# mixer.net
KiCad netlist of a schematic drawn in EAGLE
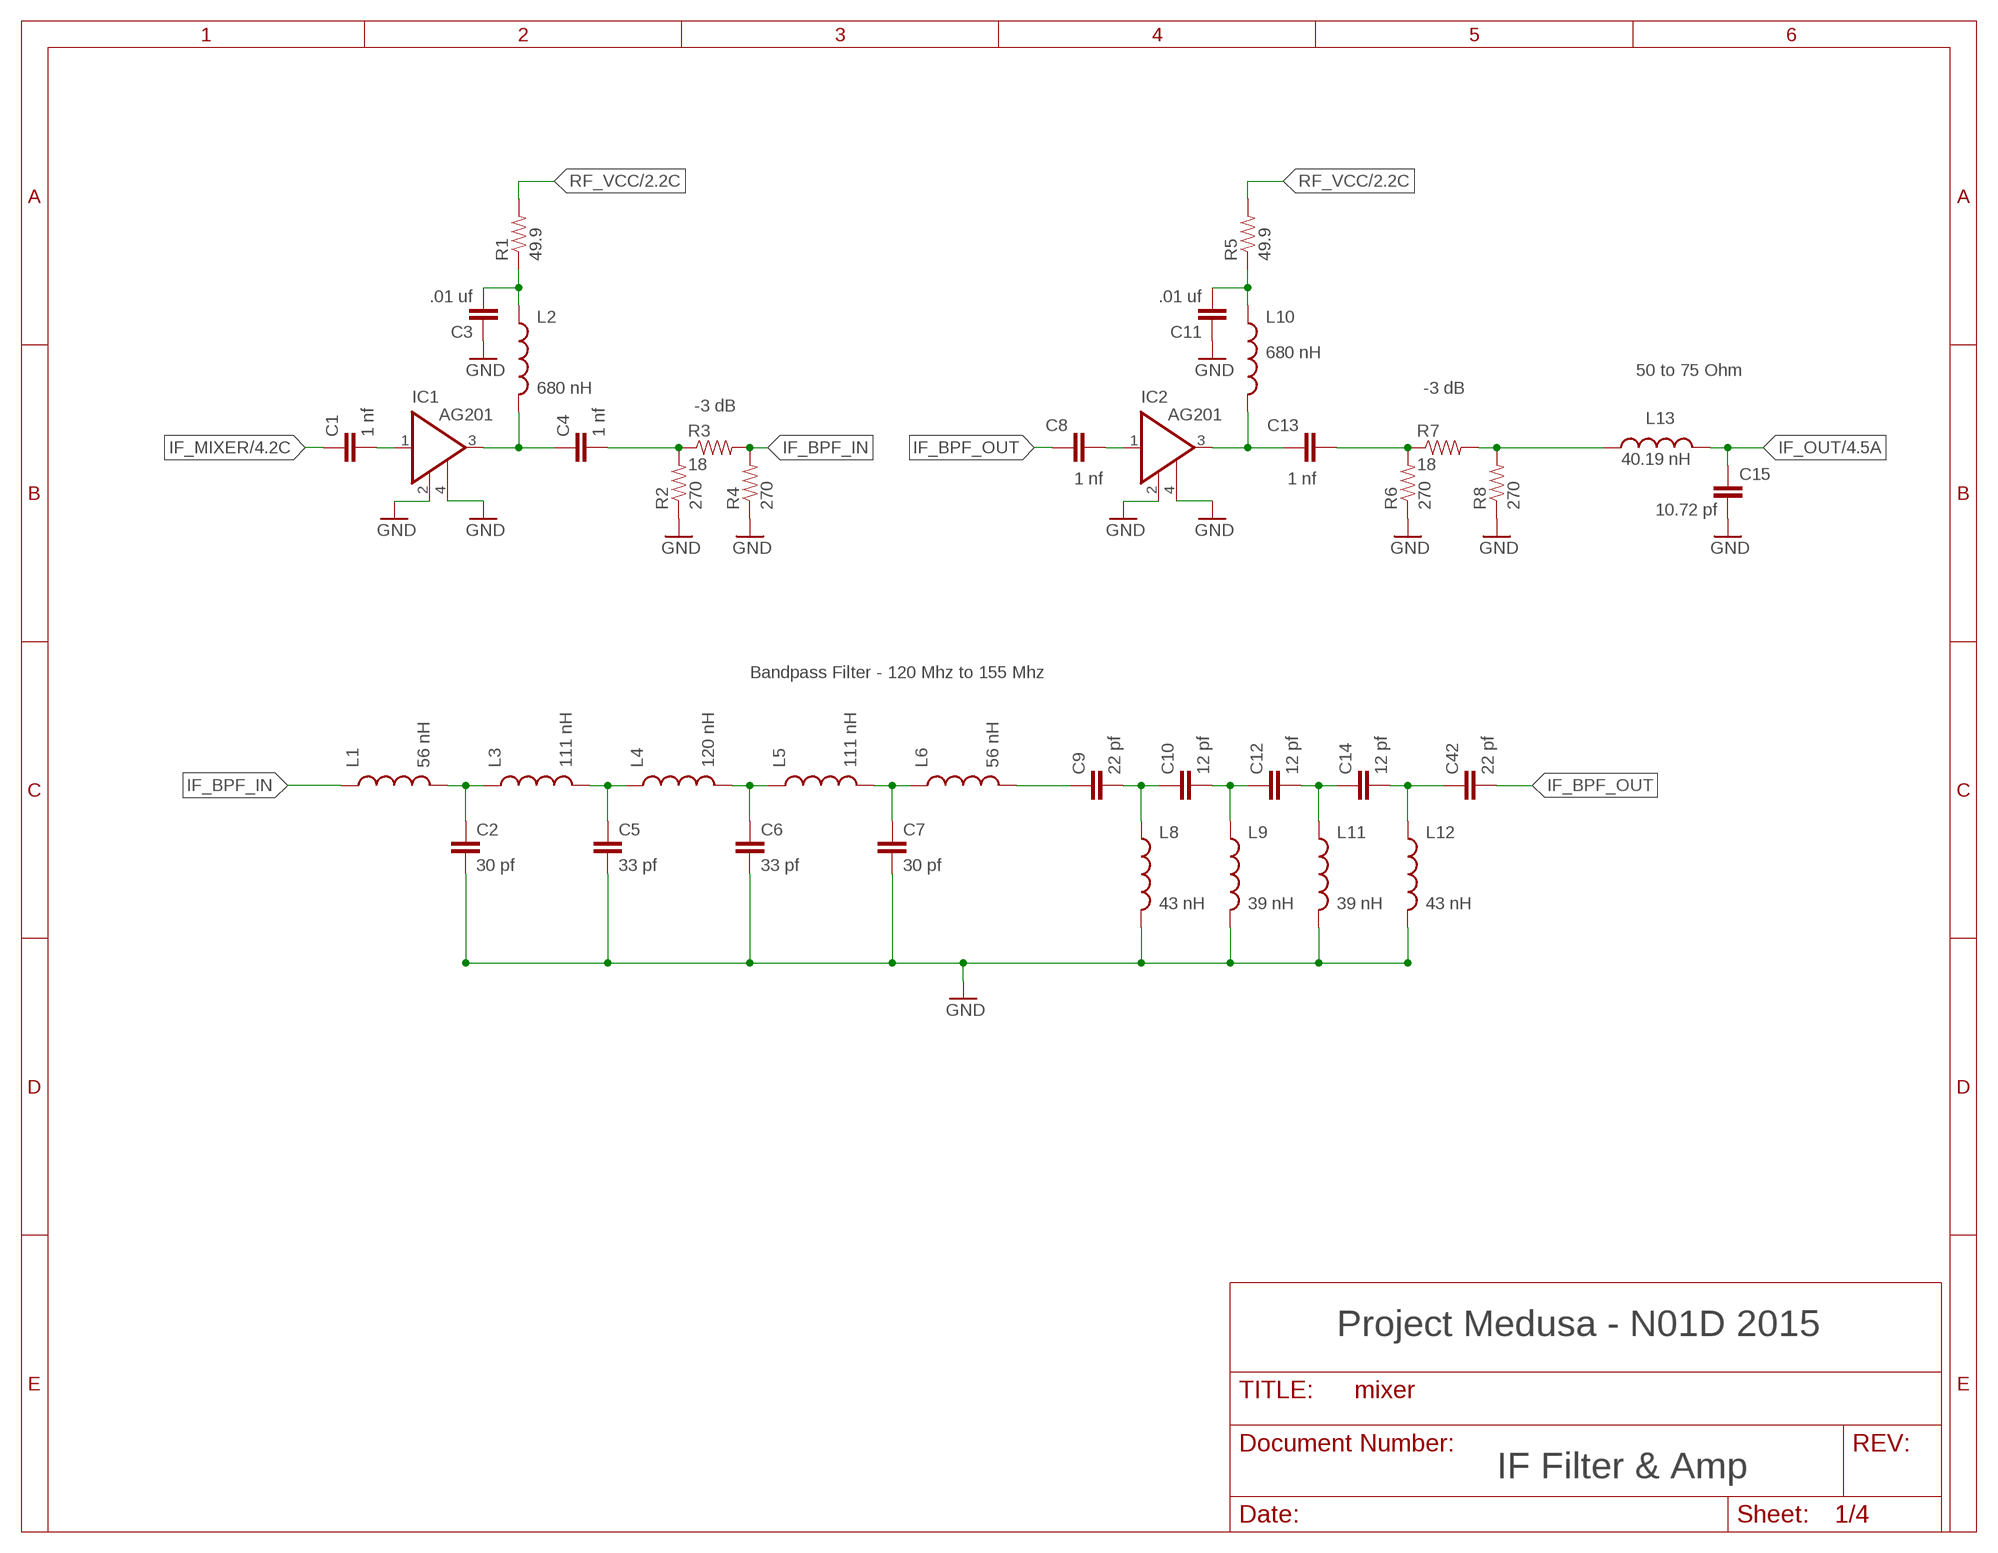
[diagram p0: schematic, sheet 1]
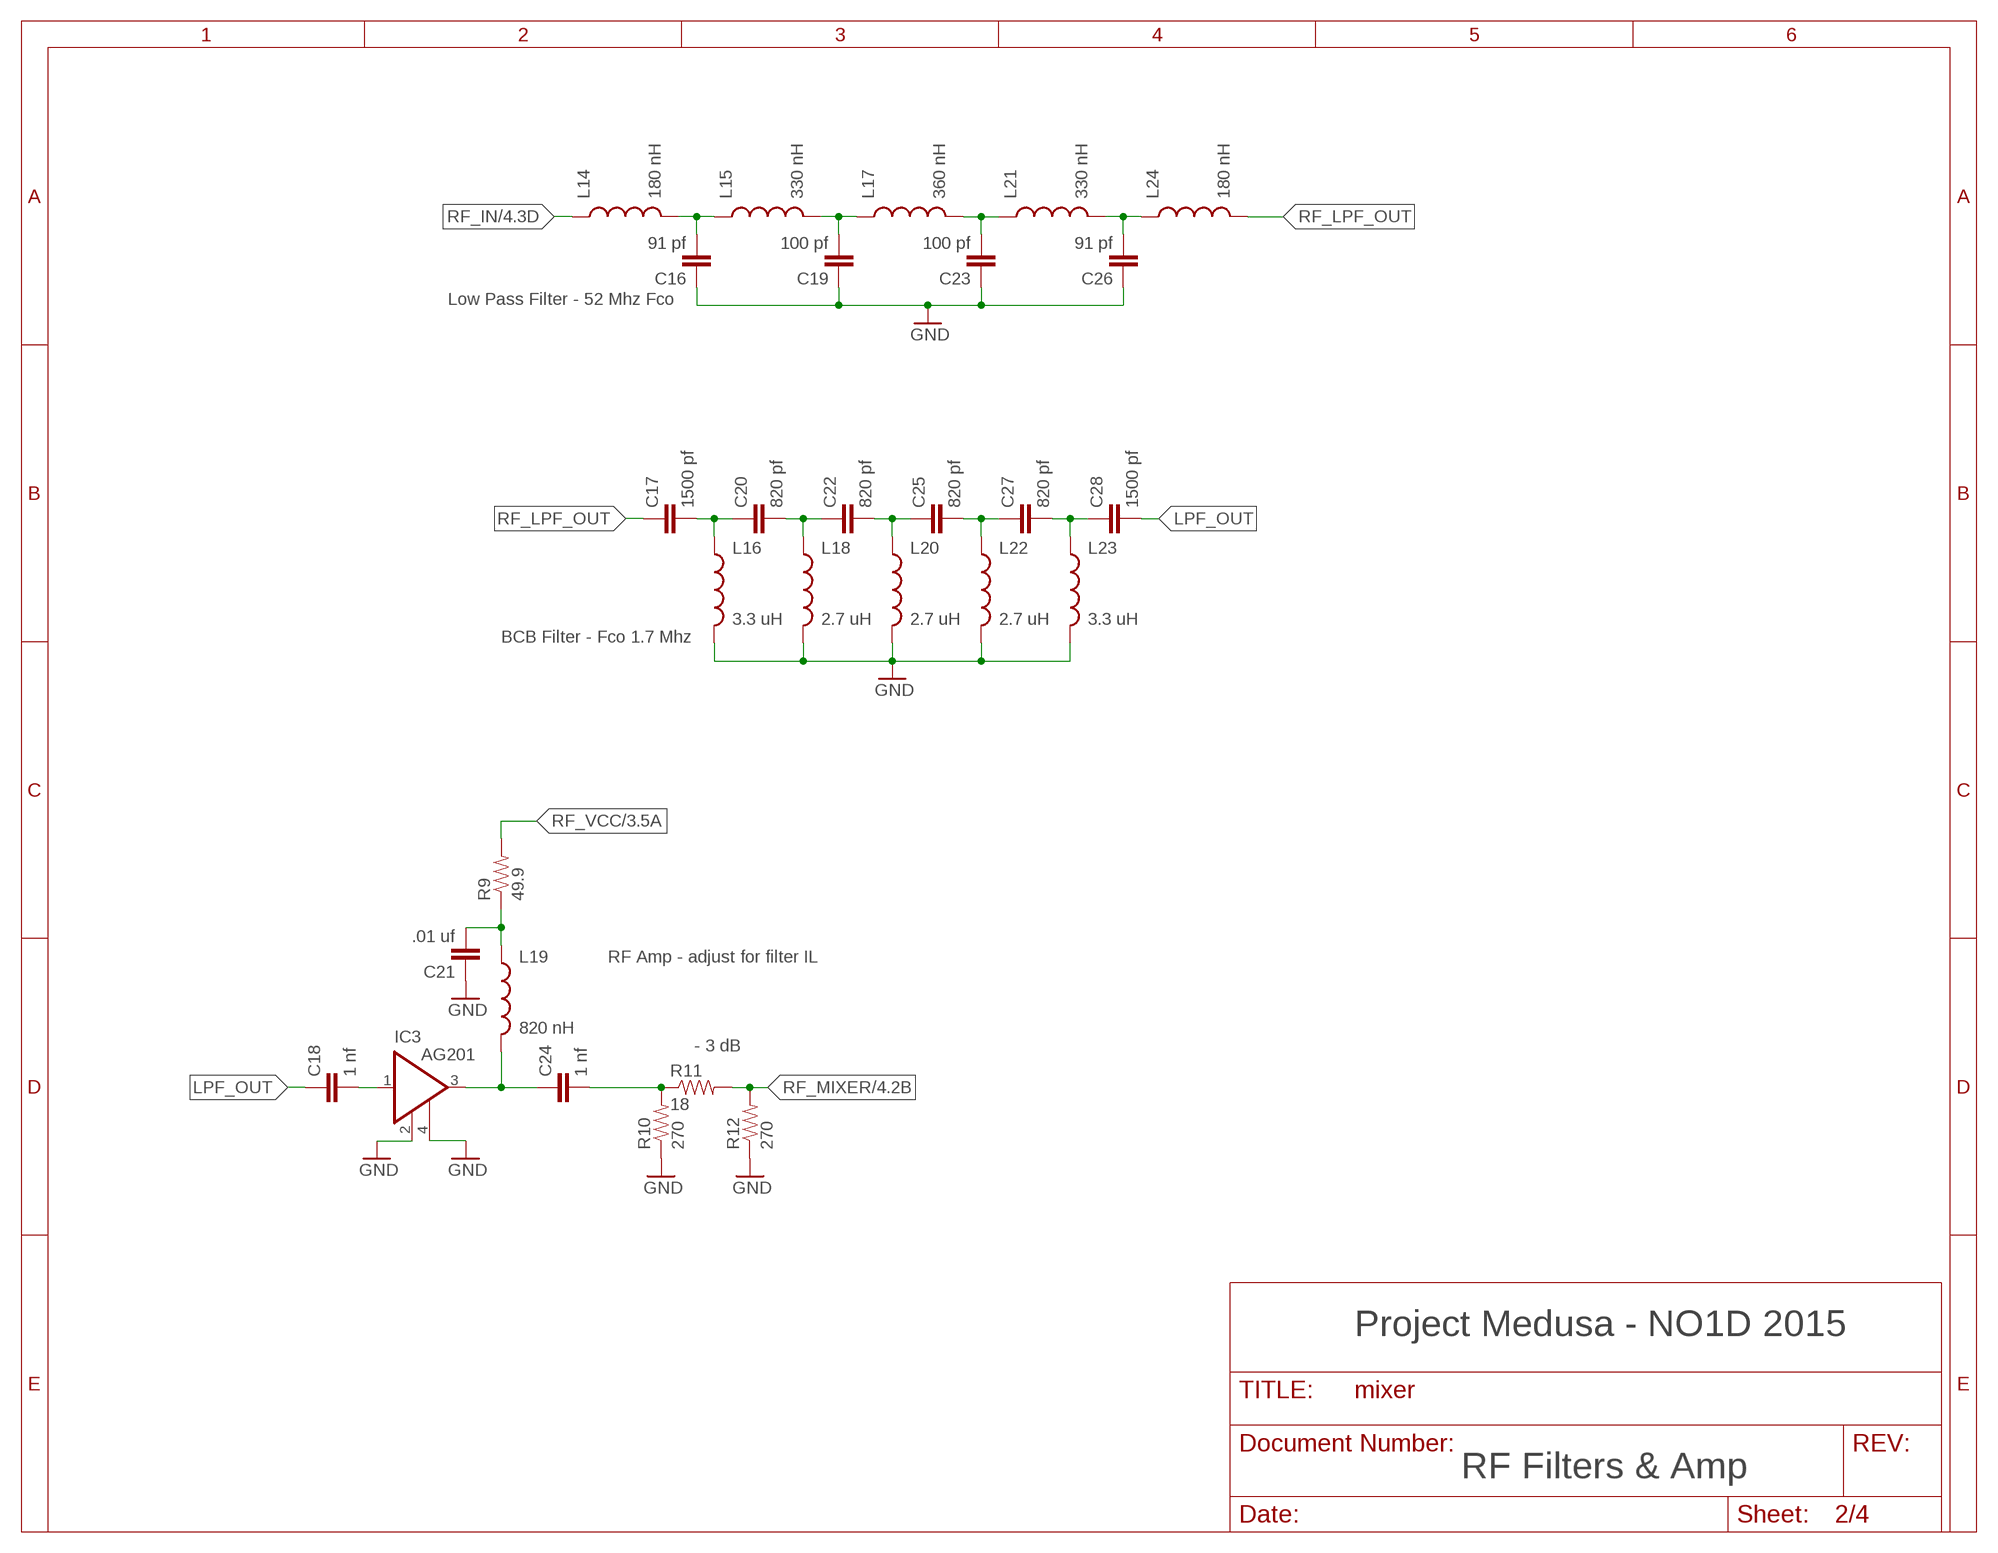
[diagram p1: schematic, sheet 2]
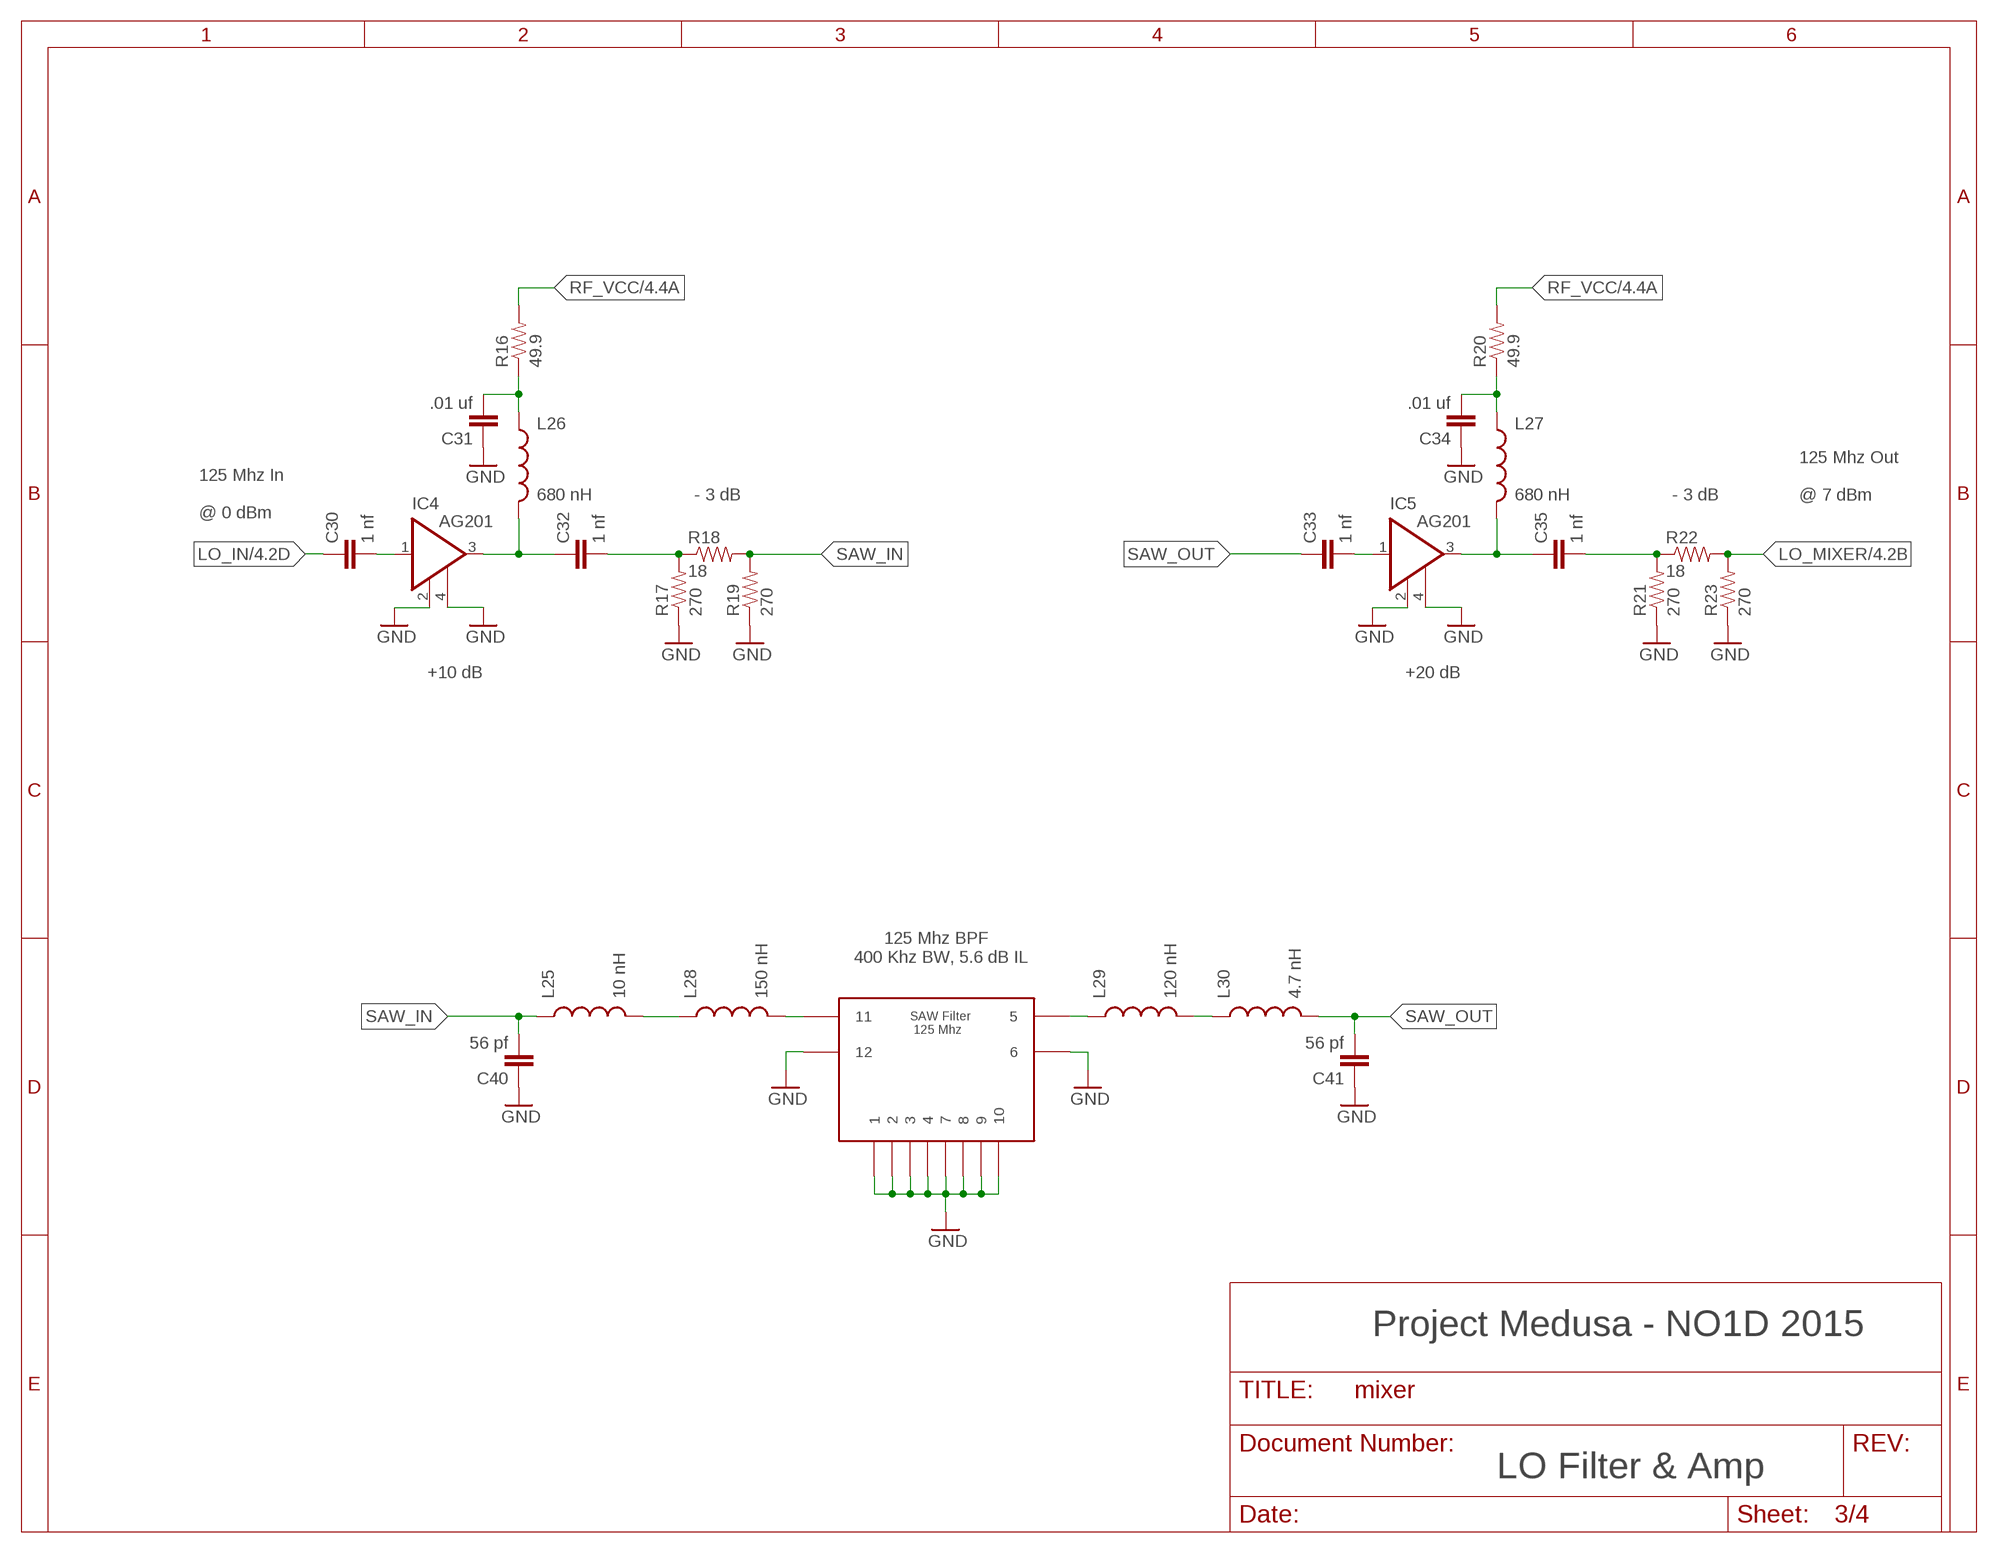
[diagram p2: schematic, sheet 3]
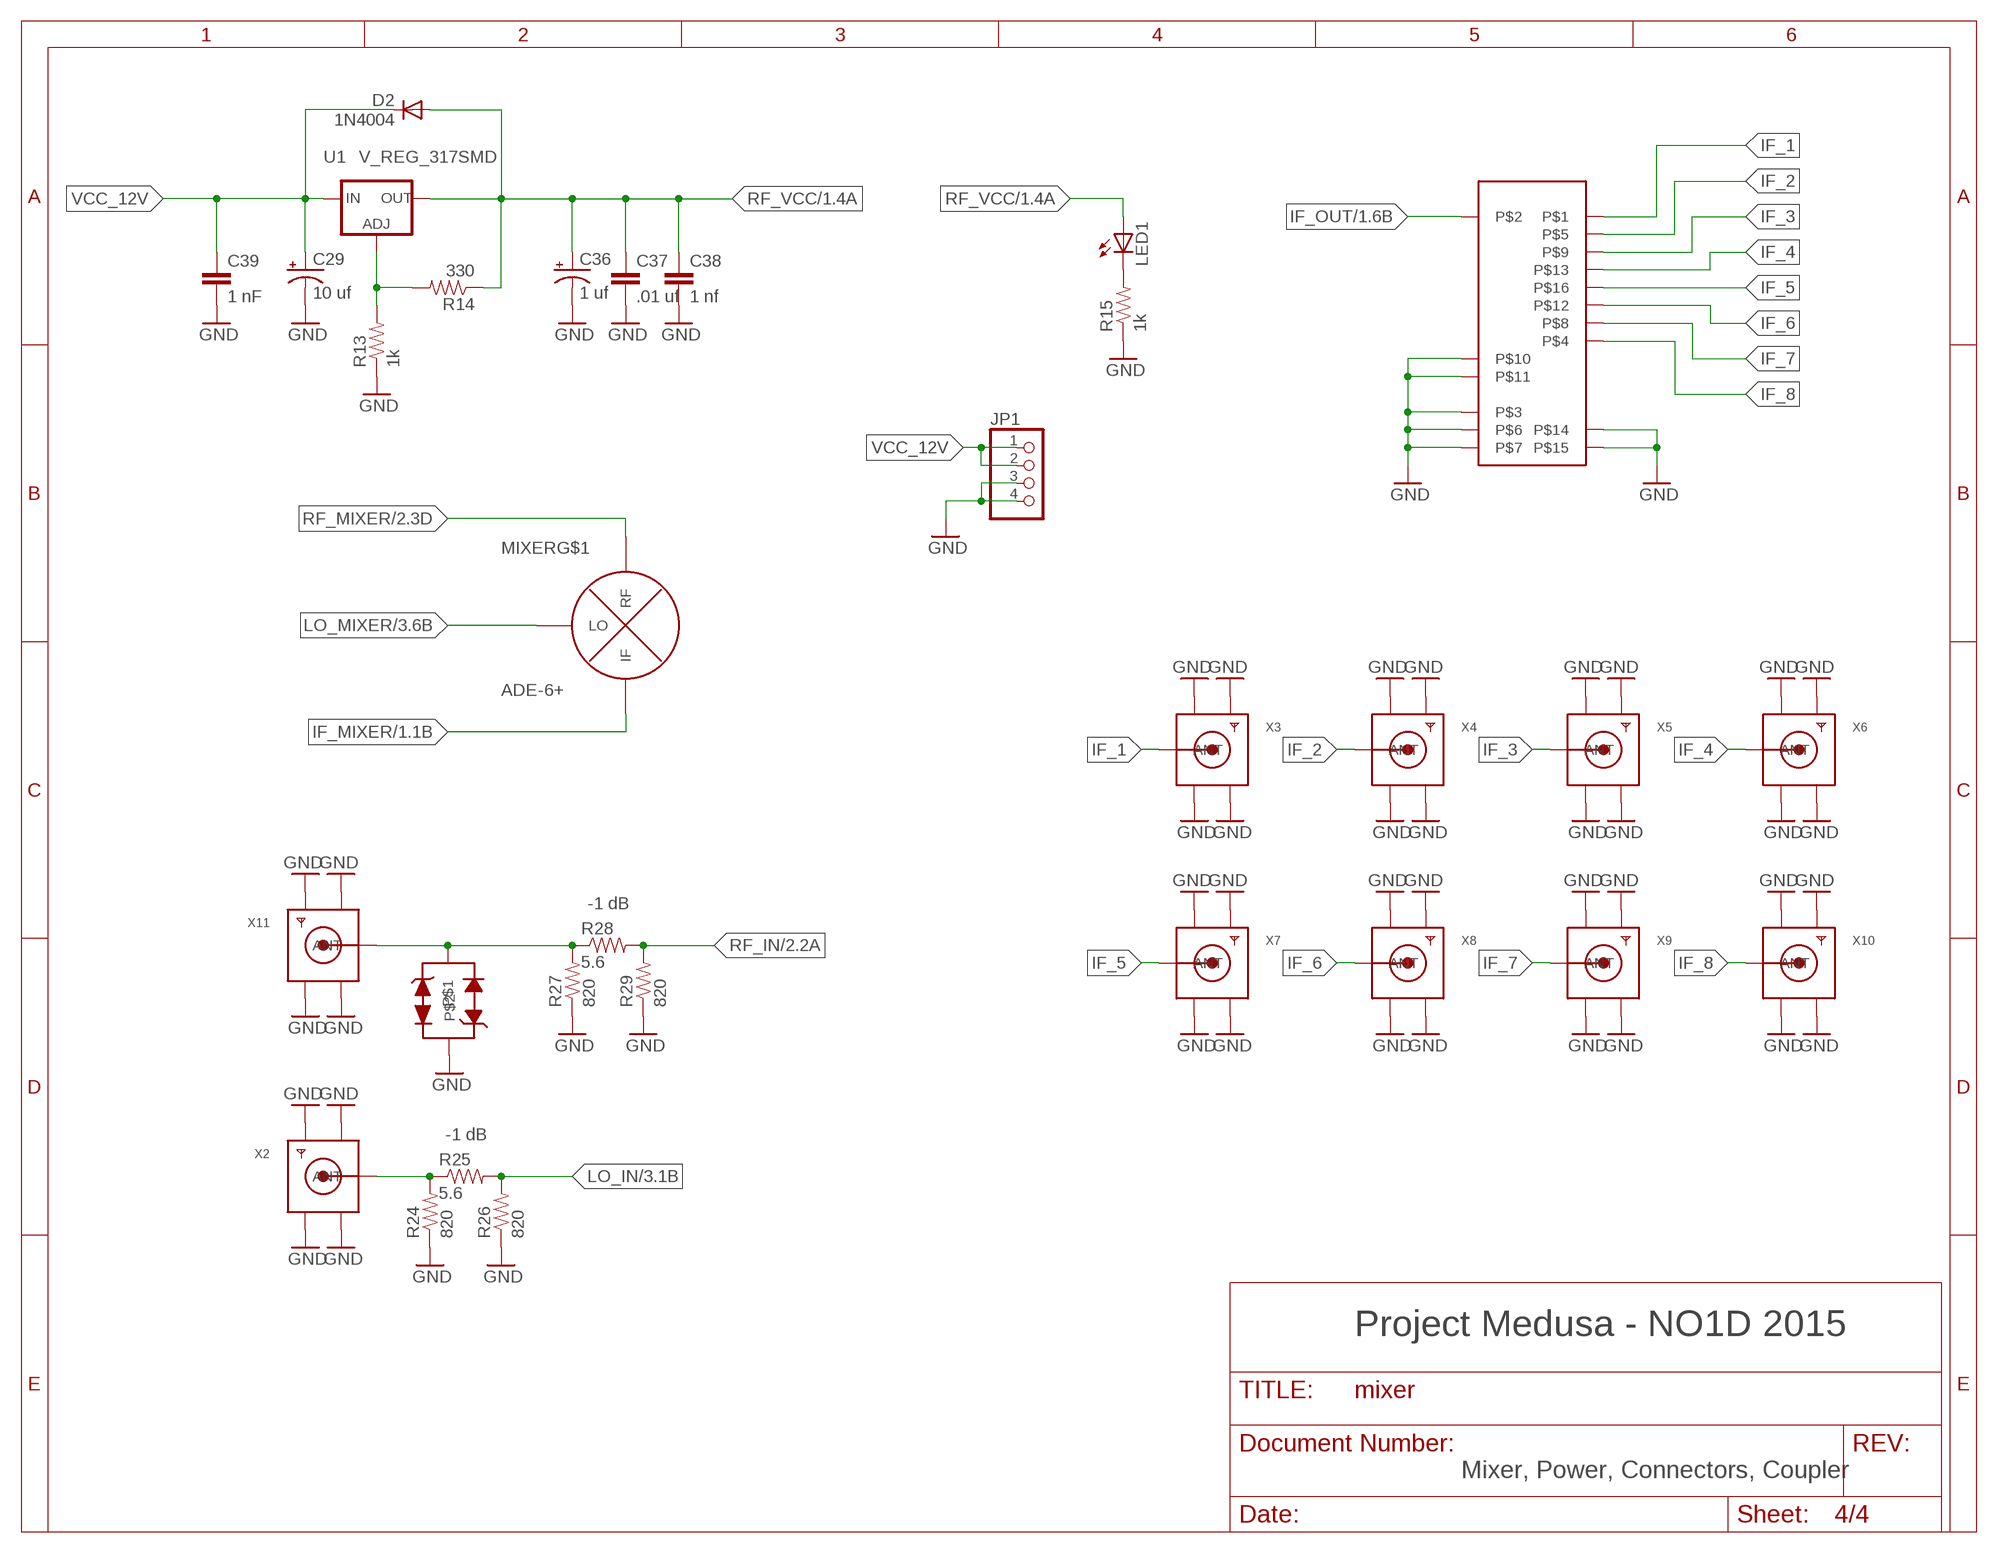
[diagram p3: schematic, sheet 4]

(export (version "E")
  (design (tool "Eeschema 10.0.6"))
  (components
    (comp (ref "C29")
      (value "10 uf")
      (footprint "eagle-import:EIA3216")
      (libsource (lib "eagle-import") (part "CAP_POL1206"))
    )
    (comp (ref "C36")
      (value "1 uf")
      (footprint "eagle-import:EIA3216")
      (libsource (lib "eagle-import") (part "CAP_POL1206"))
    )
    (comp (ref "C37")
      (value ".01 uf")
      (footprint "eagle-import:0805")
      (libsource (lib "eagle-import") (part "SparkFun-Passives_CAP0805"))
    )
    (comp (ref "C38")
      (value "1 nf")
      (footprint "eagle-import:0805")
      (libsource (lib "eagle-import") (part "SparkFun-Passives_CAP0805"))
    )
    (comp (ref "C39")
      (value "1 nF")
      (footprint "eagle-import:0805")
      (libsource (lib "eagle-import") (part "SparkFun-Passives_CAP0805"))
    )
    (comp (ref "D2")
      (value "1N4004")
      (footprint "eagle-import:DO41-10")
      (libsource (lib "eagle-import") (part "1N4004"))
    )
    (comp (ref "JP1")
      (value "PINHD-1X4")
      (footprint "eagle-import:1X04")
      (libsource (lib "eagle-import") (part "PINHD-1X4"))
    )
    (comp (ref "LED1")
      (value "LEDSML0805")
      (footprint "eagle-import:SML0805")
      (libsource (lib "eagle-import") (part "LEDSML0805"))
    )
    (comp (ref "MIXER")
      (value "ADE-6+")
      (footprint "eagle-import:ADE6")
      (libsource (lib "eagle-import") (part "ADE-6"))
    )
    (comp (ref "R13")
      (value "1k")
      (footprint "eagle-import:1206")
      (libsource (lib "eagle-import") (part "RESISTOR1206"))
    )
    (comp (ref "R14")
      (value "330")
      (footprint "eagle-import:1206")
      (libsource (lib "eagle-import") (part "RESISTOR1206"))
    )
    (comp (ref "R15")
      (value "1k")
      (footprint "eagle-import:1206")
      (libsource (lib "eagle-import") (part "RESISTOR1206"))
    )
    (comp (ref "R24")
      (value "820")
      (footprint "eagle-import:1206")
      (libsource (lib "eagle-import") (part "RESISTOR1206"))
    )
    (comp (ref "R25")
      (value "5.6")
      (footprint "eagle-import:1206")
      (libsource (lib "eagle-import") (part "RESISTOR1206"))
    )
    (comp (ref "R26")
      (value "820")
      (footprint "eagle-import:1206")
      (libsource (lib "eagle-import") (part "RESISTOR1206"))
    )
    (comp (ref "R27")
      (value "820")
      (footprint "eagle-import:1206")
      (libsource (lib "eagle-import") (part "RESISTOR1206"))
    )
    (comp (ref "R28")
      (value "5.6")
      (footprint "eagle-import:1206")
      (libsource (lib "eagle-import") (part "RESISTOR1206"))
    )
    (comp (ref "R29")
      (value "820")
      (footprint "eagle-import:1206")
      (libsource (lib "eagle-import") (part "RESISTOR1206"))
    )
    (comp (ref "U$1")
      (value "PSC-8-1-75THROUGH_HOLE")
      (footprint "eagle-import:PSC-8-1-75")
      (libsource (lib "eagle-import") (part "PSC-8-1-75THROUGH_HOLE"))
    )
    (comp (ref "U$9")
      (value "TVS-DIODE")
      (footprint "eagle-import:SOD323")
      (libsource (lib "eagle-import") (part "TVS-DIODE"))
    )
    (comp (ref "U1")
      (value "V_REG_317SMD")
      (footprint "eagle-import:SOT223")
      (libsource (lib "eagle-import") (part "V_REG_317SMD"))
    )
    (comp (ref "X2")
      (value "SMACONNECTOR_EDGE")
      (footprint "eagle-import:SMA_EDGELAUNCH")
      (libsource (lib "eagle-import") (part "SMACONNECTOR_EDGE"))
    )
    (comp (ref "X3")
      (value "SMACONNECTOR_EDGE")
      (footprint "eagle-import:SMA_EDGELAUNCH")
      (libsource (lib "eagle-import") (part "SMACONNECTOR_EDGE"))
    )
    (comp (ref "X4")
      (value "SMACONNECTOR_EDGE")
      (footprint "eagle-import:SMA_EDGELAUNCH")
      (libsource (lib "eagle-import") (part "SMACONNECTOR_EDGE"))
    )
    (comp (ref "X5")
      (value "SMACONNECTOR_EDGE")
      (footprint "eagle-import:SMA_EDGELAUNCH")
      (libsource (lib "eagle-import") (part "SMACONNECTOR_EDGE"))
    )
    (comp (ref "X6")
      (value "SMACONNECTOR_EDGE")
      (footprint "eagle-import:SMA_EDGELAUNCH")
      (libsource (lib "eagle-import") (part "SMACONNECTOR_EDGE"))
    )
    (comp (ref "X7")
      (value "SMACONNECTOR_EDGE")
      (footprint "eagle-import:SMA_EDGELAUNCH")
      (libsource (lib "eagle-import") (part "SMACONNECTOR_EDGE"))
    )
    (comp (ref "X8")
      (value "SMACONNECTOR_EDGE")
      (footprint "eagle-import:SMA_EDGELAUNCH")
      (libsource (lib "eagle-import") (part "SMACONNECTOR_EDGE"))
    )
    (comp (ref "X9")
      (value "SMACONNECTOR_EDGE")
      (footprint "eagle-import:SMA_EDGELAUNCH")
      (libsource (lib "eagle-import") (part "SMACONNECTOR_EDGE"))
    )
    (comp (ref "X10")
      (value "SMACONNECTOR_EDGE")
      (footprint "eagle-import:SMA_EDGELAUNCH")
      (libsource (lib "eagle-import") (part "SMACONNECTOR_EDGE"))
    )
    (comp (ref "X11")
      (value "SMACONNECTOR_EDGE")
      (footprint "eagle-import:SMA_EDGELAUNCH")
      (libsource (lib "eagle-import") (part "SMACONNECTOR_EDGE"))
    )
    (comp (ref "C1")
      (value "1 nf")
      (footprint "eagle-import:0805")
      (libsource (lib "eagle-import") (part "CAP0805"))
    )
    (comp (ref "C2")
      (value "30 pf")
      (footprint "eagle-import:0805")
      (libsource (lib "eagle-import") (part "CAP0805"))
    )
    (comp (ref "C3")
      (value ".01 uf")
      (footprint "eagle-import:0805")
      (libsource (lib "eagle-import") (part "CAP0805"))
    )
    (comp (ref "C4")
      (value "1 nf")
      (footprint "eagle-import:0805")
      (libsource (lib "eagle-import") (part "CAP0805"))
    )
    (comp (ref "C5")
      (value "33 pf")
      (footprint "eagle-import:0805")
      (libsource (lib "eagle-import") (part "CAP0805"))
    )
    (comp (ref "C6")
      (value "33 pf")
      (footprint "eagle-import:0805")
      (libsource (lib "eagle-import") (part "CAP0805"))
    )
    (comp (ref "C7")
      (value "30 pf")
      (footprint "eagle-import:0805")
      (libsource (lib "eagle-import") (part "CAP0805"))
    )
    (comp (ref "C8")
      (value "1 nf")
      (footprint "eagle-import:0805")
      (libsource (lib "eagle-import") (part "CAP0805"))
    )
    (comp (ref "C9")
      (value "22 pf")
      (footprint "eagle-import:0805")
      (libsource (lib "eagle-import") (part "CAP0805"))
    )
    (comp (ref "C10")
      (value "12 pf")
      (footprint "eagle-import:0805")
      (libsource (lib "eagle-import") (part "CAP0805"))
    )
    (comp (ref "C11")
      (value ".01 uf")
      (footprint "eagle-import:0805")
      (libsource (lib "eagle-import") (part "CAP0805"))
    )
    (comp (ref "C12")
      (value "12 pf")
      (footprint "eagle-import:0805")
      (libsource (lib "eagle-import") (part "CAP0805"))
    )
    (comp (ref "C13")
      (value "1 nf")
      (footprint "eagle-import:0805")
      (libsource (lib "eagle-import") (part "CAP0805"))
    )
    (comp (ref "C14")
      (value "12 pf")
      (footprint "eagle-import:0805")
      (libsource (lib "eagle-import") (part "CAP0805"))
    )
    (comp (ref "C15")
      (value "10.72 pf")
      (footprint "eagle-import:0805")
      (libsource (lib "eagle-import") (part "CAP0805"))
    )
    (comp (ref "C42")
      (value "22 pf")
      (footprint "eagle-import:0805")
      (libsource (lib "eagle-import") (part "CAP0805"))
    )
    (comp (ref "IC1")
      (value "AG201")
      (footprint "eagle-import:WW")
      (libsource (lib "eagle-import") (part "ERA-SM6"))
    )
    (comp (ref "IC2")
      (value "AG201")
      (footprint "eagle-import:WW")
      (libsource (lib "eagle-import") (part "ERA-SM6"))
    )
    (comp (ref "L1")
      (value "56 nH")
      (footprint "eagle-import:318-2")
      (libsource (lib "eagle-import") (part "INDUCTORCOILCRAFT-318-2"))
    )
    (comp (ref "L2")
      (value "680 nH")
      (footprint "eagle-import:0805")
      (libsource (lib "eagle-import") (part "INDUCTOR0805"))
    )
    (comp (ref "L3")
      (value "111 nH")
      (footprint "eagle-import:319-2")
      (libsource (lib "eagle-import") (part "INDUCTORCOILCRAFT-319-2"))
    )
    (comp (ref "L4")
      (value "120 nH")
      (footprint "eagle-import:318-2")
      (libsource (lib "eagle-import") (part "INDUCTORCOILCRAFT-318-2"))
    )
    (comp (ref "L5")
      (value "111 nH")
      (footprint "eagle-import:319-2")
      (libsource (lib "eagle-import") (part "INDUCTORCOILCRAFT-319-2"))
    )
    (comp (ref "L6")
      (value "56 nH")
      (footprint "eagle-import:318-2")
      (libsource (lib "eagle-import") (part "INDUCTORCOILCRAFT-318-2"))
    )
    (comp (ref "L8")
      (value "43 nH")
      (footprint "eagle-import:457-43")
      (libsource (lib "eagle-import") (part "INDUCTORCOILCRAFT-457-43NH"))
    )
    (comp (ref "L9")
      (value "39 nH")
      (footprint "eagle-import:457-39")
      (libsource (lib "eagle-import") (part "INDUCTORCOILCRAFT-457-39NH"))
    )
    (comp (ref "L10")
      (value "680 nH")
      (footprint "eagle-import:0805")
      (libsource (lib "eagle-import") (part "INDUCTOR0805"))
    )
    (comp (ref "L11")
      (value "39 nH")
      (footprint "eagle-import:457-39")
      (libsource (lib "eagle-import") (part "INDUCTORCOILCRAFT-457-39NH"))
    )
    (comp (ref "L12")
      (value "43 nH")
      (footprint "eagle-import:457-43")
      (libsource (lib "eagle-import") (part "INDUCTORCOILCRAFT-457-43NH"))
    )
    (comp (ref "L13")
      (value "40.19 nH")
      (footprint "eagle-import:C0402")
      (libsource (lib "eagle-import") (part "INDUCTOR0402"))
    )
    (comp (ref "R1")
      (value "49.9")
      (footprint "eagle-import:0805")
      (libsource (lib "eagle-import") (part "RESISTOR0805-RES"))
    )
    (comp (ref "R2")
      (value "270")
      (footprint "eagle-import:1206")
      (libsource (lib "eagle-import") (part "RESISTOR1206"))
    )
    (comp (ref "R3")
      (value "18")
      (footprint "eagle-import:1206")
      (libsource (lib "eagle-import") (part "RESISTOR1206"))
    )
    (comp (ref "R4")
      (value "270")
      (footprint "eagle-import:1206")
      (libsource (lib "eagle-import") (part "RESISTOR1206"))
    )
    (comp (ref "R5")
      (value "49.9")
      (footprint "eagle-import:0805")
      (libsource (lib "eagle-import") (part "RESISTOR0805-RES"))
    )
    (comp (ref "R6")
      (value "270")
      (footprint "eagle-import:1206")
      (libsource (lib "eagle-import") (part "RESISTOR1206"))
    )
    (comp (ref "R7")
      (value "18")
      (footprint "eagle-import:1206")
      (libsource (lib "eagle-import") (part "RESISTOR1206"))
    )
    (comp (ref "R8")
      (value "270")
      (footprint "eagle-import:1206")
      (libsource (lib "eagle-import") (part "RESISTOR1206"))
    )
    (comp (ref "C16")
      (value "91 pf")
      (footprint "eagle-import:0805")
      (libsource (lib "eagle-import") (part "CAP0805"))
    )
    (comp (ref "C17")
      (value "1500 pf")
      (footprint "eagle-import:0805")
      (libsource (lib "eagle-import") (part "CAP0805"))
    )
    (comp (ref "C18")
      (value "1 nf")
      (footprint "eagle-import:0805")
      (libsource (lib "eagle-import") (part "CAP0805"))
    )
    (comp (ref "C19")
      (value "100 pf")
      (footprint "eagle-import:0805")
      (libsource (lib "eagle-import") (part "CAP0805"))
    )
    (comp (ref "C20")
      (value "820 pf")
      (footprint "eagle-import:0805")
      (libsource (lib "eagle-import") (part "CAP0805"))
    )
    (comp (ref "C21")
      (value ".01 uf")
      (footprint "eagle-import:0805")
      (libsource (lib "eagle-import") (part "CAP0805"))
    )
    (comp (ref "C22")
      (value "820 pf")
      (footprint "eagle-import:0805")
      (libsource (lib "eagle-import") (part "CAP0805"))
    )
    (comp (ref "C23")
      (value "100 pf")
      (footprint "eagle-import:0805")
      (libsource (lib "eagle-import") (part "CAP0805"))
    )
    (comp (ref "C24")
      (value "1 nf")
      (footprint "eagle-import:0805")
      (libsource (lib "eagle-import") (part "CAP0805"))
    )
    (comp (ref "C25")
      (value "820 pf")
      (footprint "eagle-import:0805")
      (libsource (lib "eagle-import") (part "CAP0805"))
    )
    (comp (ref "C26")
      (value "91 pf")
      (footprint "eagle-import:0805")
      (libsource (lib "eagle-import") (part "CAP0805"))
    )
    (comp (ref "C27")
      (value "820 pf")
      (footprint "eagle-import:0805")
      (libsource (lib "eagle-import") (part "CAP0805"))
    )
    (comp (ref "C28")
      (value "1500 pf")
      (footprint "eagle-import:0805")
      (libsource (lib "eagle-import") (part "CAP0805"))
    )
    (comp (ref "IC3")
      (value "AG201")
      (footprint "eagle-import:WW")
      (libsource (lib "eagle-import") (part "ERA-SM6"))
    )
    (comp (ref "L14")
      (value "180 nH")
      (footprint "eagle-import:438-2-180")
      (libsource (lib "eagle-import") (part "INDUCTORCOILCRAFT-438-2-180"))
    )
    (comp (ref "L15")
      (value "330 nH")
      (footprint "eagle-import:438-2-330")
      (libsource (lib "eagle-import") (part "INDUCTORCOILCRAFT-438-2-330"))
    )
    (comp (ref "L16")
      (value "3.3 uH")
      (footprint "eagle-import:RLB0912")
      (libsource (lib "eagle-import") (part "INDUCTORRLB0912"))
    )
    (comp (ref "L17")
      (value "360 nH")
      (footprint "eagle-import:438-2-360")
      (libsource (lib "eagle-import") (part "INDUCTORCOILCRAFT-438-2-360"))
    )
    (comp (ref "L18")
      (value "2.7 uH")
      (footprint "eagle-import:RLB0912")
      (libsource (lib "eagle-import") (part "INDUCTORRLB0912"))
    )
    (comp (ref "L19")
      (value "820 nH")
      (footprint "eagle-import:0805")
      (libsource (lib "eagle-import") (part "INDUCTOR0805"))
    )
    (comp (ref "L20")
      (value "2.7 uH")
      (footprint "eagle-import:RLB0912")
      (libsource (lib "eagle-import") (part "INDUCTORRLB0912"))
    )
    (comp (ref "L21")
      (value "330 nH")
      (footprint "eagle-import:438-2-330")
      (libsource (lib "eagle-import") (part "INDUCTORCOILCRAFT-438-2-330"))
    )
    (comp (ref "L22")
      (value "2.7 uH")
      (footprint "eagle-import:RLB0912")
      (libsource (lib "eagle-import") (part "INDUCTORRLB0912"))
    )
    (comp (ref "L23")
      (value "3.3 uH")
      (footprint "eagle-import:RLB0912")
      (libsource (lib "eagle-import") (part "INDUCTORRLB0912"))
    )
    (comp (ref "L24")
      (value "180 nH")
      (footprint "eagle-import:438-2-180")
      (libsource (lib "eagle-import") (part "INDUCTORCOILCRAFT-438-2-180"))
    )
    (comp (ref "R9")
      (value "49.9")
      (footprint "eagle-import:0805")
      (libsource (lib "eagle-import") (part "RESISTOR0805-RES"))
    )
    (comp (ref "R10")
      (value "270")
      (footprint "eagle-import:1206")
      (libsource (lib "eagle-import") (part "RESISTOR1206"))
    )
    (comp (ref "R11")
      (value "18")
      (footprint "eagle-import:1206")
      (libsource (lib "eagle-import") (part "RESISTOR1206"))
    )
    (comp (ref "R12")
      (value "270")
      (footprint "eagle-import:1206")
      (libsource (lib "eagle-import") (part "RESISTOR1206"))
    )
    (comp (ref "C30")
      (value "1 nf")
      (footprint "eagle-import:0805")
      (libsource (lib "eagle-import") (part "CAP0805"))
    )
    (comp (ref "C31")
      (value ".01 uf")
      (footprint "eagle-import:0805")
      (libsource (lib "eagle-import") (part "CAP0805"))
    )
    (comp (ref "C32")
      (value "1 nf")
      (footprint "eagle-import:0805")
      (libsource (lib "eagle-import") (part "CAP0805"))
    )
    (comp (ref "C33")
      (value "1 nf")
      (footprint "eagle-import:0805")
      (libsource (lib "eagle-import") (part "CAP0805"))
    )
    (comp (ref "C34")
      (value ".01 uf")
      (footprint "eagle-import:0805")
      (libsource (lib "eagle-import") (part "CAP0805"))
    )
    (comp (ref "C35")
      (value "1 nf")
      (footprint "eagle-import:0805")
      (libsource (lib "eagle-import") (part "CAP0805"))
    )
    (comp (ref "C40")
      (value "56 pf")
      (footprint "eagle-import:0805")
      (libsource (lib "eagle-import") (part "CAP0805"))
    )
    (comp (ref "C41")
      (value "56 pf")
      (footprint "eagle-import:0805")
      (libsource (lib "eagle-import") (part "CAP0805"))
    )
    (comp (ref "IC4")
      (value "AG201")
      (footprint "eagle-import:WW")
      (libsource (lib "eagle-import") (part "ERA-SM6"))
    )
    (comp (ref "IC5")
      (value "AG201")
      (footprint "eagle-import:WW")
      (libsource (lib "eagle-import") (part "ERA-SM6"))
    )
    (comp (ref "L25")
      (value "10 nH")
      (footprint "eagle-import:C0402")
      (libsource (lib "eagle-import") (part "INDUCTOR0402"))
    )
    (comp (ref "L26")
      (value "680 nH")
      (footprint "eagle-import:0805")
      (libsource (lib "eagle-import") (part "INDUCTOR0805"))
    )
    (comp (ref "L27")
      (value "680 nH")
      (footprint "eagle-import:0805")
      (libsource (lib "eagle-import") (part "INDUCTOR0805"))
    )
    (comp (ref "L28")
      (value "150 nH")
      (footprint "eagle-import:0805")
      (libsource (lib "eagle-import") (part "INDUCTOR0805"))
    )
    (comp (ref "L29")
      (value "120 nH")
      (footprint "eagle-import:0805")
      (libsource (lib "eagle-import") (part "INDUCTOR0805"))
    )
    (comp (ref "L30")
      (value "4.7 nH")
      (footprint "eagle-import:C0402")
      (libsource (lib "eagle-import") (part "INDUCTOR0402"))
    )
    (comp (ref "R16")
      (value "49.9")
      (footprint "eagle-import:0805")
      (libsource (lib "eagle-import") (part "RESISTOR0805-RES"))
    )
    (comp (ref "R17")
      (value "270")
      (footprint "eagle-import:1206")
      (libsource (lib "eagle-import") (part "RESISTOR1206"))
    )
    (comp (ref "R18")
      (value "18")
      (footprint "eagle-import:1206")
      (libsource (lib "eagle-import") (part "RESISTOR1206"))
    )
    (comp (ref "R19")
      (value "270")
      (footprint "eagle-import:1206")
      (libsource (lib "eagle-import") (part "RESISTOR1206"))
    )
    (comp (ref "R20")
      (value "49.9")
      (footprint "eagle-import:0805")
      (libsource (lib "eagle-import") (part "RESISTOR0805-RES"))
    )
    (comp (ref "R21")
      (value "270")
      (footprint "eagle-import:1206")
      (libsource (lib "eagle-import") (part "RESISTOR1206"))
    )
    (comp (ref "R22")
      (value "18")
      (footprint "eagle-import:1206")
      (libsource (lib "eagle-import") (part "RESISTOR1206"))
    )
    (comp (ref "R23")
      (value "270")
      (footprint "eagle-import:1206")
      (libsource (lib "eagle-import") (part "RESISTOR1206"))
    )
    (comp (ref "SAW1")
      (value "SAW-125MHZ")
      (footprint "eagle-import:SAW-125M-SMP")
      (libsource (lib "eagle-import") (part "SAW-125MHZ"))
    )
  )
  (nets
    (net (code "1") (name "GND") (class "Default")
      (node (ref "C11") (pin "1") (pinfunction "1_1") (pintype "passive"))
      (node (ref "C15") (pin "1") (pinfunction "1_1") (pintype "passive"))
      (node (ref "C16") (pin "1") (pinfunction "1_1") (pintype "passive"))
      (node (ref "C19") (pin "1") (pinfunction "1_1") (pintype "passive"))
      (node (ref "C2") (pin "2") (pinfunction "2_2") (pintype "passive"))
      (node (ref "C21") (pin "1") (pinfunction "1_1") (pintype "passive"))
      (node (ref "C23") (pin "1") (pinfunction "1_1") (pintype "passive"))
      (node (ref "C26") (pin "1") (pinfunction "1_1") (pintype "passive"))
      (node (ref "C29") (pin "C") (pinfunction "-_C") (pintype "passive"))
      (node (ref "C3") (pin "1") (pinfunction "1_1") (pintype "passive"))
      (node (ref "C31") (pin "1") (pinfunction "1_1") (pintype "passive"))
      (node (ref "C34") (pin "1") (pinfunction "1_1") (pintype "passive"))
      (node (ref "C36") (pin "C") (pinfunction "-_C") (pintype "passive"))
      (node (ref "C37") (pin "2") (pinfunction "2_2") (pintype "passive"))
      (node (ref "C38") (pin "2") (pinfunction "2_2") (pintype "passive"))
      (node (ref "C39") (pin "2") (pinfunction "2_2") (pintype "passive"))
      (node (ref "C40") (pin "1") (pinfunction "1_1") (pintype "passive"))
      (node (ref "C41") (pin "1") (pinfunction "1_1") (pintype "passive"))
      (node (ref "C5") (pin "2") (pinfunction "2_2") (pintype "passive"))
      (node (ref "C6") (pin "2") (pinfunction "2_2") (pintype "passive"))
      (node (ref "C7") (pin "2") (pinfunction "2_2") (pintype "passive"))
      (node (ref "IC1") (pin "2") (pinfunction "GND_2") (pintype "power_in"))
      (node (ref "IC1") (pin "4") (pinfunction "GND_4") (pintype "power_in"))
      (node (ref "IC2") (pin "2") (pinfunction "GND_2") (pintype "power_in"))
      (node (ref "IC2") (pin "4") (pinfunction "GND_4") (pintype "power_in"))
      (node (ref "IC3") (pin "2") (pinfunction "GND_2") (pintype "power_in"))
      (node (ref "IC3") (pin "4") (pinfunction "GND_4") (pintype "power_in"))
      (node (ref "IC4") (pin "2") (pinfunction "GND_2") (pintype "power_in"))
      (node (ref "IC4") (pin "4") (pinfunction "GND_4") (pintype "power_in"))
      (node (ref "IC5") (pin "2") (pinfunction "GND_2") (pintype "power_in"))
      (node (ref "IC5") (pin "4") (pinfunction "GND_4") (pintype "power_in"))
      (node (ref "JP1") (pin "3") (pinfunction "3_3") (pintype "passive"))
      (node (ref "JP1") (pin "4") (pinfunction "4_4") (pintype "passive"))
      (node (ref "L11") (pin "P$2") (pinfunction "2_P$2") (pintype "passive"))
      (node (ref "L12") (pin "P$2") (pinfunction "2_P$2") (pintype "passive"))
      (node (ref "L16") (pin "2") (pinfunction "2_2") (pintype "passive"))
      (node (ref "L18") (pin "2") (pinfunction "2_2") (pintype "passive"))
      (node (ref "L20") (pin "2") (pinfunction "2_2") (pintype "passive"))
      (node (ref "L22") (pin "2") (pinfunction "2_2") (pintype "passive"))
      (node (ref "L23") (pin "2") (pinfunction "2_2") (pintype "passive"))
      (node (ref "L8") (pin "P$2") (pinfunction "2_P$2") (pintype "passive"))
      (node (ref "L9") (pin "P$2") (pinfunction "2_P$2") (pintype "passive"))
      (node (ref "R10") (pin "1") (pinfunction "1_1") (pintype "passive"))
      (node (ref "R12") (pin "1") (pinfunction "1_1") (pintype "passive"))
      (node (ref "R13") (pin "1") (pinfunction "1_1") (pintype "passive"))
      (node (ref "R15") (pin "1") (pinfunction "1_1") (pintype "passive"))
      (node (ref "R17") (pin "1") (pinfunction "1_1") (pintype "passive"))
      (node (ref "R19") (pin "1") (pinfunction "1_1") (pintype "passive"))
      (node (ref "R2") (pin "1") (pinfunction "1_1") (pintype "passive"))
      (node (ref "R21") (pin "1") (pinfunction "1_1") (pintype "passive"))
      (node (ref "R23") (pin "1") (pinfunction "1_1") (pintype "passive"))
      (node (ref "R24") (pin "1") (pinfunction "1_1") (pintype "passive"))
      (node (ref "R26") (pin "1") (pinfunction "1_1") (pintype "passive"))
      (node (ref "R27") (pin "1") (pinfunction "1_1") (pintype "passive"))
      (node (ref "R29") (pin "1") (pinfunction "1_1") (pintype "passive"))
      (node (ref "R4") (pin "1") (pinfunction "1_1") (pintype "passive"))
      (node (ref "R6") (pin "1") (pinfunction "1_1") (pintype "passive"))
      (node (ref "R8") (pin "1") (pinfunction "1_1") (pintype "passive"))
      (node (ref "SAW1") (pin "P$1") (pinfunction "1_P$1") (pintype "bidirectional"))
      (node (ref "SAW1") (pin "P$10") (pinfunction "10_P$10") (pintype "bidirectional"))
      (node (ref "SAW1") (pin "P$12") (pinfunction "12_P$12") (pintype "bidirectional"))
      (node (ref "SAW1") (pin "P$2") (pinfunction "2_P$2") (pintype "bidirectional"))
      (node (ref "SAW1") (pin "P$3") (pinfunction "3_P$3") (pintype "bidirectional"))
      (node (ref "SAW1") (pin "P$4") (pinfunction "4_P$4") (pintype "bidirectional"))
      (node (ref "SAW1") (pin "P$6") (pinfunction "6_P$6") (pintype "bidirectional"))
      (node (ref "SAW1") (pin "P$7") (pinfunction "7_P$7") (pintype "bidirectional"))
      (node (ref "SAW1") (pin "P$8") (pinfunction "8_P$8") (pintype "bidirectional"))
      (node (ref "SAW1") (pin "P$9") (pinfunction "9_P$9") (pintype "bidirectional"))
      (node (ref "U$1") (pin "P$10") (pinfunction "P$10_P$10") (pintype "bidirectional"))
      (node (ref "U$1") (pin "P$11") (pinfunction "P$11_P$11") (pintype "bidirectional"))
      (node (ref "U$1") (pin "P$14") (pinfunction "P$14_P$14") (pintype "bidirectional"))
      (node (ref "U$1") (pin "P$15") (pinfunction "P$15_P$15") (pintype "bidirectional"))
      (node (ref "U$1") (pin "P$3") (pinfunction "P$3_P$3") (pintype "bidirectional"))
      (node (ref "U$1") (pin "P$6") (pinfunction "P$6_P$6") (pintype "bidirectional"))
      (node (ref "U$1") (pin "P$7") (pinfunction "P$7_P$7") (pintype "bidirectional"))
      (node (ref "U$9") (pin "P$3") (pinfunction "P$2_P$3") (pintype "bidirectional"))
      (node (ref "X10") (pin "GND@1") (pinfunction "GND4_GND@1") (pintype "power_in"))
      (node (ref "X10") (pin "GND@2") (pinfunction "GND3_GND@2") (pintype "power_in"))
      (node (ref "X10") (pin "GND@3") (pinfunction "GND2_GND@3") (pintype "power_in"))
      (node (ref "X10") (pin "GND@4") (pinfunction "GND1_GND@4") (pintype "power_in"))
      (node (ref "X11") (pin "GND@1") (pinfunction "GND4_GND@1") (pintype "power_in"))
      (node (ref "X11") (pin "GND@2") (pinfunction "GND3_GND@2") (pintype "power_in"))
      (node (ref "X11") (pin "GND@3") (pinfunction "GND2_GND@3") (pintype "power_in"))
      (node (ref "X11") (pin "GND@4") (pinfunction "GND1_GND@4") (pintype "power_in"))
      (node (ref "X2") (pin "GND@1") (pinfunction "GND4_GND@1") (pintype "power_in"))
      (node (ref "X2") (pin "GND@2") (pinfunction "GND3_GND@2") (pintype "power_in"))
      (node (ref "X2") (pin "GND@3") (pinfunction "GND2_GND@3") (pintype "power_in"))
      (node (ref "X2") (pin "GND@4") (pinfunction "GND1_GND@4") (pintype "power_in"))
      (node (ref "X3") (pin "GND@1") (pinfunction "GND4_GND@1") (pintype "power_in"))
      (node (ref "X3") (pin "GND@2") (pinfunction "GND3_GND@2") (pintype "power_in"))
      (node (ref "X3") (pin "GND@3") (pinfunction "GND2_GND@3") (pintype "power_in"))
      (node (ref "X3") (pin "GND@4") (pinfunction "GND1_GND@4") (pintype "power_in"))
      (node (ref "X4") (pin "GND@1") (pinfunction "GND4_GND@1") (pintype "power_in"))
      (node (ref "X4") (pin "GND@2") (pinfunction "GND3_GND@2") (pintype "power_in"))
      (node (ref "X4") (pin "GND@3") (pinfunction "GND2_GND@3") (pintype "power_in"))
      (node (ref "X4") (pin "GND@4") (pinfunction "GND1_GND@4") (pintype "power_in"))
      (node (ref "X5") (pin "GND@1") (pinfunction "GND4_GND@1") (pintype "power_in"))
      (node (ref "X5") (pin "GND@2") (pinfunction "GND3_GND@2") (pintype "power_in"))
      (node (ref "X5") (pin "GND@3") (pinfunction "GND2_GND@3") (pintype "power_in"))
      (node (ref "X5") (pin "GND@4") (pinfunction "GND1_GND@4") (pintype "power_in"))
      (node (ref "X6") (pin "GND@1") (pinfunction "GND4_GND@1") (pintype "power_in"))
      (node (ref "X6") (pin "GND@2") (pinfunction "GND3_GND@2") (pintype "power_in"))
      (node (ref "X6") (pin "GND@3") (pinfunction "GND2_GND@3") (pintype "power_in"))
      (node (ref "X6") (pin "GND@4") (pinfunction "GND1_GND@4") (pintype "power_in"))
      (node (ref "X7") (pin "GND@1") (pinfunction "GND4_GND@1") (pintype "power_in"))
      (node (ref "X7") (pin "GND@2") (pinfunction "GND3_GND@2") (pintype "power_in"))
      (node (ref "X7") (pin "GND@3") (pinfunction "GND2_GND@3") (pintype "power_in"))
      (node (ref "X7") (pin "GND@4") (pinfunction "GND1_GND@4") (pintype "power_in"))
      (node (ref "X8") (pin "GND@1") (pinfunction "GND4_GND@1") (pintype "power_in"))
      (node (ref "X8") (pin "GND@2") (pinfunction "GND3_GND@2") (pintype "power_in"))
      (node (ref "X8") (pin "GND@3") (pinfunction "GND2_GND@3") (pintype "power_in"))
      (node (ref "X8") (pin "GND@4") (pinfunction "GND1_GND@4") (pintype "power_in"))
      (node (ref "X9") (pin "GND@1") (pinfunction "GND4_GND@1") (pintype "power_in"))
      (node (ref "X9") (pin "GND@2") (pinfunction "GND3_GND@2") (pintype "power_in"))
      (node (ref "X9") (pin "GND@3") (pinfunction "GND2_GND@3") (pintype "power_in"))
      (node (ref "X9") (pin "GND@4") (pinfunction "GND1_GND@4") (pintype "power_in"))
    )
    (net (code "2") (name "IF_1") (class "Default")
      (node (ref "U$1") (pin "P$1") (pinfunction "P$1_P$1") (pintype "bidirectional"))
      (node (ref "X3") (pin "P") (pinfunction "ANT_P") (pintype "bidirectional"))
    )
    (net (code "3") (name "IF_2") (class "Default")
      (node (ref "U$1") (pin "P$5") (pinfunction "P$5_P$5") (pintype "bidirectional"))
      (node (ref "X4") (pin "P") (pinfunction "ANT_P") (pintype "bidirectional"))
    )
    (net (code "4") (name "IF_3") (class "Default")
      (node (ref "U$1") (pin "P$9") (pinfunction "P$9_P$9") (pintype "bidirectional"))
      (node (ref "X5") (pin "P") (pinfunction "ANT_P") (pintype "bidirectional"))
    )
    (net (code "5") (name "IF_4") (class "Default")
      (node (ref "U$1") (pin "P$13") (pinfunction "P$13_P$13") (pintype "bidirectional"))
      (node (ref "X6") (pin "P") (pinfunction "ANT_P") (pintype "bidirectional"))
    )
    (net (code "6") (name "IF_5") (class "Default")
      (node (ref "U$1") (pin "P$16") (pinfunction "P$16_P$16") (pintype "bidirectional"))
      (node (ref "X7") (pin "P") (pinfunction "ANT_P") (pintype "bidirectional"))
    )
    (net (code "7") (name "IF_6") (class "Default")
      (node (ref "U$1") (pin "P$12") (pinfunction "P$12_P$12") (pintype "bidirectional"))
      (node (ref "X8") (pin "P") (pinfunction "ANT_P") (pintype "bidirectional"))
    )
    (net (code "8") (name "IF_7") (class "Default")
      (node (ref "U$1") (pin "P$8") (pinfunction "P$8_P$8") (pintype "bidirectional"))
      (node (ref "X9") (pin "P") (pinfunction "ANT_P") (pintype "bidirectional"))
    )
    (net (code "9") (name "IF_8") (class "Default")
      (node (ref "U$1") (pin "P$4") (pinfunction "P$4_P$4") (pintype "bidirectional"))
      (node (ref "X10") (pin "P") (pinfunction "ANT_P") (pintype "bidirectional"))
    )
    (net (code "10") (name "IF_BPF_IN") (class "Default")
      (node (ref "L1") (pin "P$1") (pinfunction "1_P$1") (pintype "passive"))
      (node (ref "R3") (pin "2") (pinfunction "2_2") (pintype "passive"))
      (node (ref "R4") (pin "2") (pinfunction "2_2") (pintype "passive"))
    )
    (net (code "11") (name "IF_BPF_OUT") (class "Default")
      (node (ref "C42") (pin "2") (pinfunction "2_2") (pintype "passive"))
      (node (ref "C8") (pin "1") (pinfunction "1_1") (pintype "passive"))
    )
    (net (code "12") (name "IF_MIXER") (class "Default")
      (node (ref "C1") (pin "1") (pinfunction "1_1") (pintype "passive"))
      (node (ref "MIXER") (pin "P$2") (pinfunction "IF_P$2") (pintype "bidirectional"))
    )
    (net (code "13") (name "IF_OUT") (class "Default")
      (node (ref "C15") (pin "2") (pinfunction "2_2") (pintype "passive"))
      (node (ref "L13") (pin "2") (pinfunction "2_2") (pintype "passive"))
      (node (ref "U$1") (pin "P$2") (pinfunction "P$2_P$2") (pintype "bidirectional"))
    )
    (net (code "14") (name "LO_IN") (class "Default")
      (node (ref "C30") (pin "1") (pinfunction "1_1") (pintype "passive"))
      (node (ref "R25") (pin "2") (pinfunction "2_2") (pintype "passive"))
      (node (ref "R26") (pin "2") (pinfunction "2_2") (pintype "passive"))
    )
    (net (code "15") (name "LO_MIXER") (class "Default")
      (node (ref "MIXER") (pin "P$6") (pinfunction "LO_P$6") (pintype "bidirectional"))
      (node (ref "R22") (pin "2") (pinfunction "2_2") (pintype "passive"))
      (node (ref "R23") (pin "2") (pinfunction "2_2") (pintype "passive"))
    )
    (net (code "16") (name "LPF_OUT") (class "Default")
      (node (ref "C18") (pin "1") (pinfunction "1_1") (pintype "passive"))
      (node (ref "C28") (pin "2") (pinfunction "2_2") (pintype "passive"))
    )
    (net (code "17") (name "Net-(C3-Pad2)") (class "Default")
      (node (ref "C3") (pin "2") (pinfunction "2_2") (pintype "passive"))
      (node (ref "L2") (pin "1") (pinfunction "1_1") (pintype "passive"))
      (node (ref "R1") (pin "1") (pinfunction "1_1") (pintype "passive"))
    )
    (net (code "18") (name "Net-(C4-Pad2)") (class "Default")
      (node (ref "C4") (pin "2") (pinfunction "2_2") (pintype "passive"))
      (node (ref "R2") (pin "2") (pinfunction "2_2") (pintype "passive"))
      (node (ref "R3") (pin "1") (pinfunction "1_1") (pintype "passive"))
    )
    (net (code "19") (name "Net-(C11-Pad2)") (class "Default")
      (node (ref "C11") (pin "2") (pinfunction "2_2") (pintype "passive"))
      (node (ref "L10") (pin "1") (pinfunction "1_1") (pintype "passive"))
      (node (ref "R5") (pin "1") (pinfunction "1_1") (pintype "passive"))
    )
    (net (code "20") (name "Net-(C13-Pad2)") (class "Default")
      (node (ref "C13") (pin "2") (pinfunction "2_2") (pintype "passive"))
      (node (ref "R6") (pin "2") (pinfunction "2_2") (pintype "passive"))
      (node (ref "R7") (pin "1") (pinfunction "1_1") (pintype "passive"))
    )
    (net (code "21") (name "Net-(C17-Pad2)") (class "Default")
      (node (ref "C17") (pin "2") (pinfunction "2_2") (pintype "passive"))
      (node (ref "C20") (pin "1") (pinfunction "1_1") (pintype "passive"))
      (node (ref "L16") (pin "1") (pinfunction "1_1") (pintype "passive"))
    )
    (net (code "22") (name "Net-(C20-Pad2)") (class "Default")
      (node (ref "C20") (pin "2") (pinfunction "2_2") (pintype "passive"))
      (node (ref "C22") (pin "1") (pinfunction "1_1") (pintype "passive"))
      (node (ref "L18") (pin "1") (pinfunction "1_1") (pintype "passive"))
    )
    (net (code "23") (name "Net-(C21-Pad2)") (class "Default")
      (node (ref "C21") (pin "2") (pinfunction "2_2") (pintype "passive"))
      (node (ref "L19") (pin "1") (pinfunction "1_1") (pintype "passive"))
      (node (ref "R9") (pin "1") (pinfunction "1_1") (pintype "passive"))
    )
    (net (code "24") (name "Net-(C22-Pad2)") (class "Default")
      (node (ref "C22") (pin "2") (pinfunction "2_2") (pintype "passive"))
      (node (ref "C25") (pin "1") (pinfunction "1_1") (pintype "passive"))
      (node (ref "L20") (pin "1") (pinfunction "1_1") (pintype "passive"))
    )
    (net (code "25") (name "Net-(C24-Pad2)") (class "Default")
      (node (ref "C24") (pin "2") (pinfunction "2_2") (pintype "passive"))
      (node (ref "R10") (pin "2") (pinfunction "2_2") (pintype "passive"))
      (node (ref "R11") (pin "1") (pinfunction "1_1") (pintype "passive"))
    )
    (net (code "26") (name "Net-(C25-Pad2)") (class "Default")
      (node (ref "C25") (pin "2") (pinfunction "2_2") (pintype "passive"))
      (node (ref "C27") (pin "1") (pinfunction "1_1") (pintype "passive"))
      (node (ref "L22") (pin "1") (pinfunction "1_1") (pintype "passive"))
    )
    (net (code "27") (name "Net-(C27-Pad2)") (class "Default")
      (node (ref "C27") (pin "2") (pinfunction "2_2") (pintype "passive"))
      (node (ref "C28") (pin "1") (pinfunction "1_1") (pintype "passive"))
      (node (ref "L23") (pin "1") (pinfunction "1_1") (pintype "passive"))
    )
    (net (code "28") (name "Net-(C31-Pad2)") (class "Default")
      (node (ref "C31") (pin "2") (pinfunction "2_2") (pintype "passive"))
      (node (ref "L26") (pin "1") (pinfunction "1_1") (pintype "passive"))
      (node (ref "R16") (pin "1") (pinfunction "1_1") (pintype "passive"))
    )
    (net (code "29") (name "Net-(C32-Pad2)") (class "Default")
      (node (ref "C32") (pin "2") (pinfunction "2_2") (pintype "passive"))
      (node (ref "R17") (pin "2") (pinfunction "2_2") (pintype "passive"))
      (node (ref "R18") (pin "1") (pinfunction "1_1") (pintype "passive"))
    )
    (net (code "30") (name "Net-(C34-Pad2)") (class "Default")
      (node (ref "C34") (pin "2") (pinfunction "2_2") (pintype "passive"))
      (node (ref "L27") (pin "1") (pinfunction "1_1") (pintype "passive"))
      (node (ref "R20") (pin "1") (pinfunction "1_1") (pintype "passive"))
    )
    (net (code "31") (name "Net-(C35-Pad2)") (class "Default")
      (node (ref "C35") (pin "2") (pinfunction "2_2") (pintype "passive"))
      (node (ref "R21") (pin "2") (pinfunction "2_2") (pintype "passive"))
      (node (ref "R22") (pin "1") (pinfunction "1_1") (pintype "passive"))
    )
    (net (code "32") (name "Net-(IC1-RFIN)") (class "Default")
      (node (ref "C1") (pin "2") (pinfunction "2_2") (pintype "passive"))
      (node (ref "IC1") (pin "1") (pinfunction "RFIN_1") (pintype "input"))
    )
    (net (code "33") (name "Net-(IC1-RFOUT{slash}DCIN)") (class "Default")
      (node (ref "C4") (pin "1") (pinfunction "1_1") (pintype "passive"))
      (node (ref "IC1") (pin "3") (pinfunction "RFOUT/DCIN_3") (pintype "output"))
      (node (ref "L2") (pin "2") (pinfunction "2_2") (pintype "passive"))
    )
    (net (code "34") (name "Net-(IC2-RFIN)") (class "Default")
      (node (ref "C8") (pin "2") (pinfunction "2_2") (pintype "passive"))
      (node (ref "IC2") (pin "1") (pinfunction "RFIN_1") (pintype "input"))
    )
    (net (code "35") (name "Net-(IC2-RFOUT{slash}DCIN)") (class "Default")
      (node (ref "C13") (pin "1") (pinfunction "1_1") (pintype "passive"))
      (node (ref "IC2") (pin "3") (pinfunction "RFOUT/DCIN_3") (pintype "output"))
      (node (ref "L10") (pin "2") (pinfunction "2_2") (pintype "passive"))
    )
    (net (code "36") (name "Net-(IC3-RFIN)") (class "Default")
      (node (ref "C18") (pin "2") (pinfunction "2_2") (pintype "passive"))
      (node (ref "IC3") (pin "1") (pinfunction "RFIN_1") (pintype "input"))
    )
    (net (code "37") (name "Net-(IC3-RFOUT{slash}DCIN)") (class "Default")
      (node (ref "C24") (pin "1") (pinfunction "1_1") (pintype "passive"))
      (node (ref "IC3") (pin "3") (pinfunction "RFOUT/DCIN_3") (pintype "output"))
      (node (ref "L19") (pin "2") (pinfunction "2_2") (pintype "passive"))
    )
    (net (code "38") (name "Net-(IC4-RFIN)") (class "Default")
      (node (ref "C30") (pin "2") (pinfunction "2_2") (pintype "passive"))
      (node (ref "IC4") (pin "1") (pinfunction "RFIN_1") (pintype "input"))
    )
    (net (code "39") (name "Net-(IC4-RFOUT{slash}DCIN)") (class "Default")
      (node (ref "C32") (pin "1") (pinfunction "1_1") (pintype "passive"))
      (node (ref "IC4") (pin "3") (pinfunction "RFOUT/DCIN_3") (pintype "output"))
      (node (ref "L26") (pin "2") (pinfunction "2_2") (pintype "passive"))
    )
    (net (code "40") (name "Net-(IC5-RFIN)") (class "Default")
      (node (ref "C33") (pin "2") (pinfunction "2_2") (pintype "passive"))
      (node (ref "IC5") (pin "1") (pinfunction "RFIN_1") (pintype "input"))
    )
    (net (code "41") (name "Net-(IC5-RFOUT{slash}DCIN)") (class "Default")
      (node (ref "C35") (pin "1") (pinfunction "1_1") (pintype "passive"))
      (node (ref "IC5") (pin "3") (pinfunction "RFOUT/DCIN_3") (pintype "output"))
      (node (ref "L27") (pin "2") (pinfunction "2_2") (pintype "passive"))
    )
    (net (code "42") (name "Net-(L1-2)") (class "Default")
      (node (ref "C2") (pin "1") (pinfunction "1_1") (pintype "passive"))
      (node (ref "L1") (pin "P$2") (pinfunction "2_P$2") (pintype "passive"))
      (node (ref "L3") (pin "P$1") (pinfunction "1_P$1") (pintype "passive"))
    )
    (net (code "43") (name "Net-(L3-2)") (class "Default")
      (node (ref "C5") (pin "1") (pinfunction "1_1") (pintype "passive"))
      (node (ref "L3") (pin "P$2") (pinfunction "2_P$2") (pintype "passive"))
      (node (ref "L4") (pin "P$1") (pinfunction "1_P$1") (pintype "passive"))
    )
    (net (code "44") (name "Net-(L4-2)") (class "Default")
      (node (ref "C6") (pin "1") (pinfunction "1_1") (pintype "passive"))
      (node (ref "L4") (pin "P$2") (pinfunction "2_P$2") (pintype "passive"))
      (node (ref "L5") (pin "P$1") (pinfunction "1_P$1") (pintype "passive"))
    )
    (net (code "45") (name "Net-(L5-2)") (class "Default")
      (node (ref "C7") (pin "1") (pinfunction "1_1") (pintype "passive"))
      (node (ref "L5") (pin "P$2") (pinfunction "2_P$2") (pintype "passive"))
      (node (ref "L6") (pin "P$1") (pinfunction "1_P$1") (pintype "passive"))
    )
    (net (code "46") (name "Net-(L6-2)") (class "Default")
      (node (ref "C9") (pin "1") (pinfunction "1_1") (pintype "passive"))
      (node (ref "L6") (pin "P$2") (pinfunction "2_P$2") (pintype "passive"))
    )
    (net (code "47") (name "Net-(L8-1)") (class "Default")
      (node (ref "C10") (pin "1") (pinfunction "1_1") (pintype "passive"))
      (node (ref "C9") (pin "2") (pinfunction "2_2") (pintype "passive"))
      (node (ref "L8") (pin "P$1") (pinfunction "1_P$1") (pintype "passive"))
    )
    (net (code "48") (name "Net-(L9-1)") (class "Default")
      (node (ref "C10") (pin "2") (pinfunction "2_2") (pintype "passive"))
      (node (ref "C12") (pin "1") (pinfunction "1_1") (pintype "passive"))
      (node (ref "L9") (pin "P$1") (pinfunction "1_P$1") (pintype "passive"))
    )
    (net (code "49") (name "Net-(L11-1)") (class "Default")
      (node (ref "C12") (pin "2") (pinfunction "2_2") (pintype "passive"))
      (node (ref "C14") (pin "1") (pinfunction "1_1") (pintype "passive"))
      (node (ref "L11") (pin "P$1") (pinfunction "1_P$1") (pintype "passive"))
    )
    (net (code "50") (name "Net-(L12-1)") (class "Default")
      (node (ref "C14") (pin "2") (pinfunction "2_2") (pintype "passive"))
      (node (ref "C42") (pin "1") (pinfunction "1_1") (pintype "passive"))
      (node (ref "L12") (pin "P$1") (pinfunction "1_P$1") (pintype "passive"))
    )
    (net (code "51") (name "Net-(L13-Pad1)") (class "Default")
      (node (ref "L13") (pin "1") (pinfunction "1_1") (pintype "passive"))
      (node (ref "R7") (pin "2") (pinfunction "2_2") (pintype "passive"))
      (node (ref "R8") (pin "2") (pinfunction "2_2") (pintype "passive"))
    )
    (net (code "52") (name "Net-(L14-2)") (class "Default")
      (node (ref "C16") (pin "2") (pinfunction "2_2") (pintype "passive"))
      (node (ref "L14") (pin "P$2") (pinfunction "2_P$2") (pintype "passive"))
      (node (ref "L15") (pin "P$1") (pinfunction "1_P$1") (pintype "passive"))
    )
    (net (code "53") (name "Net-(L15-2)") (class "Default")
      (node (ref "C19") (pin "2") (pinfunction "2_2") (pintype "passive"))
      (node (ref "L15") (pin "P$2") (pinfunction "2_P$2") (pintype "passive"))
      (node (ref "L17") (pin "P$1") (pinfunction "1_P$1") (pintype "passive"))
    )
    (net (code "54") (name "Net-(L17-2)") (class "Default")
      (node (ref "C23") (pin "2") (pinfunction "2_2") (pintype "passive"))
      (node (ref "L17") (pin "P$2") (pinfunction "2_P$2") (pintype "passive"))
      (node (ref "L21") (pin "P$1") (pinfunction "1_P$1") (pintype "passive"))
    )
    (net (code "55") (name "Net-(L21-2)") (class "Default")
      (node (ref "C26") (pin "2") (pinfunction "2_2") (pintype "passive"))
      (node (ref "L21") (pin "P$2") (pinfunction "2_P$2") (pintype "passive"))
      (node (ref "L24") (pin "P$1") (pinfunction "1_P$1") (pintype "passive"))
    )
    (net (code "56") (name "Net-(L25-Pad2)") (class "Default")
      (node (ref "L25") (pin "2") (pinfunction "2_2") (pintype "passive"))
      (node (ref "L28") (pin "1") (pinfunction "1_1") (pintype "passive"))
    )
    (net (code "57") (name "Net-(L29-Pad2)") (class "Default")
      (node (ref "L29") (pin "2") (pinfunction "2_2") (pintype "passive"))
      (node (ref "L30") (pin "1") (pinfunction "1_1") (pintype "passive"))
    )
    (net (code "58") (name "Net-(LED1-PadC)") (class "Default")
      (node (ref "LED1") (pin "C") (pinfunction "C_C") (pintype "passive"))
      (node (ref "R15") (pin "2") (pinfunction "2_2") (pintype "passive"))
    )
    (net (code "59") (name "Net-(SAW1-5)") (class "Default")
      (node (ref "L29") (pin "1") (pinfunction "1_1") (pintype "passive"))
      (node (ref "SAW1") (pin "P$5") (pinfunction "5_P$5") (pintype "bidirectional"))
    )
    (net (code "60") (name "Net-(SAW1-11)") (class "Default")
      (node (ref "L28") (pin "2") (pinfunction "2_2") (pintype "passive"))
      (node (ref "SAW1") (pin "P$11") (pinfunction "11_P$11") (pintype "bidirectional"))
    )
    (net (code "61") (name "Net-(U1-ADJ)") (class "Default")
      (node (ref "R13") (pin "2") (pinfunction "2_2") (pintype "passive"))
      (node (ref "R14") (pin "2") (pinfunction "2_2") (pintype "passive"))
      (node (ref "U1") (pin "1") (pinfunction "ADJ_1") (pintype "input"))
    )
    (net (code "62") (name "Net-(X2-ANT)") (class "Default")
      (node (ref "R24") (pin "2") (pinfunction "2_2") (pintype "passive"))
      (node (ref "R25") (pin "1") (pinfunction "1_1") (pintype "passive"))
      (node (ref "X2") (pin "P") (pinfunction "ANT_P") (pintype "bidirectional"))
    )
    (net (code "63") (name "Net-(X11-ANT)") (class "Default")
      (node (ref "R27") (pin "2") (pinfunction "2_2") (pintype "passive"))
      (node (ref "R28") (pin "1") (pinfunction "1_1") (pintype "passive"))
      (node (ref "U$9") (pin "P$1") (pinfunction "P$1_P$1") (pintype "bidirectional"))
      (node (ref "X11") (pin "P") (pinfunction "ANT_P") (pintype "bidirectional"))
    )
    (net (code "64") (name "RF_IN") (class "Default")
      (node (ref "L14") (pin "P$1") (pinfunction "1_P$1") (pintype "passive"))
      (node (ref "R28") (pin "2") (pinfunction "2_2") (pintype "passive"))
      (node (ref "R29") (pin "2") (pinfunction "2_2") (pintype "passive"))
    )
    (net (code "65") (name "RF_LPF_OUT") (class "Default")
      (node (ref "C17") (pin "1") (pinfunction "1_1") (pintype "passive"))
      (node (ref "L24") (pin "P$2") (pinfunction "2_P$2") (pintype "passive"))
    )
    (net (code "66") (name "RF_MIXER") (class "Default")
      (node (ref "MIXER") (pin "P$3") (pinfunction "RF_P$3") (pintype "bidirectional"))
      (node (ref "R11") (pin "2") (pinfunction "2_2") (pintype "passive"))
      (node (ref "R12") (pin "2") (pinfunction "2_2") (pintype "passive"))
    )
    (net (code "67") (name "RF_VCC") (class "Default")
      (node (ref "C36") (pin "A") (pinfunction "+_A") (pintype "passive"))
      (node (ref "C37") (pin "1") (pinfunction "1_1") (pintype "passive"))
      (node (ref "C38") (pin "1") (pinfunction "1_1") (pintype "passive"))
      (node (ref "D2") (pin "A") (pinfunction "A_A") (pintype "passive"))
      (node (ref "LED1") (pin "A") (pinfunction "A_A") (pintype "passive"))
      (node (ref "R1") (pin "2") (pinfunction "2_2") (pintype "passive"))
      (node (ref "R14") (pin "1") (pinfunction "1_1") (pintype "passive"))
      (node (ref "R16") (pin "2") (pinfunction "2_2") (pintype "passive"))
      (node (ref "R20") (pin "2") (pinfunction "2_2") (pintype "passive"))
      (node (ref "R5") (pin "2") (pinfunction "2_2") (pintype "passive"))
      (node (ref "R9") (pin "2") (pinfunction "2_2") (pintype "passive"))
      (node (ref "U1") (pin "2") (pinfunction "OUT_2") (pintype "output"))
    )
    (net (code "68") (name "SAW_IN") (class "Default")
      (node (ref "C40") (pin "2") (pinfunction "2_2") (pintype "passive"))
      (node (ref "L25") (pin "1") (pinfunction "1_1") (pintype "passive"))
      (node (ref "R18") (pin "2") (pinfunction "2_2") (pintype "passive"))
      (node (ref "R19") (pin "2") (pinfunction "2_2") (pintype "passive"))
    )
    (net (code "69") (name "SAW_OUT") (class "Default")
      (node (ref "C33") (pin "1") (pinfunction "1_1") (pintype "passive"))
      (node (ref "C41") (pin "2") (pinfunction "2_2") (pintype "passive"))
      (node (ref "L30") (pin "2") (pinfunction "2_2") (pintype "passive"))
    )
    (net (code "70") (name "VCC_12V") (class "Default")
      (node (ref "C29") (pin "A") (pinfunction "+_A") (pintype "passive"))
      (node (ref "C39") (pin "1") (pinfunction "1_1") (pintype "passive"))
      (node (ref "D2") (pin "C") (pinfunction "C_C") (pintype "passive"))
      (node (ref "JP1") (pin "1") (pinfunction "1_1") (pintype "passive"))
      (node (ref "JP1") (pin "2") (pinfunction "2_2") (pintype "passive"))
      (node (ref "U1") (pin "3") (pinfunction "IN_3") (pintype "input"))
    )
  )
)
